# RT-Polit.net
KiCad netlist of a schematic drawn in Altium Designer
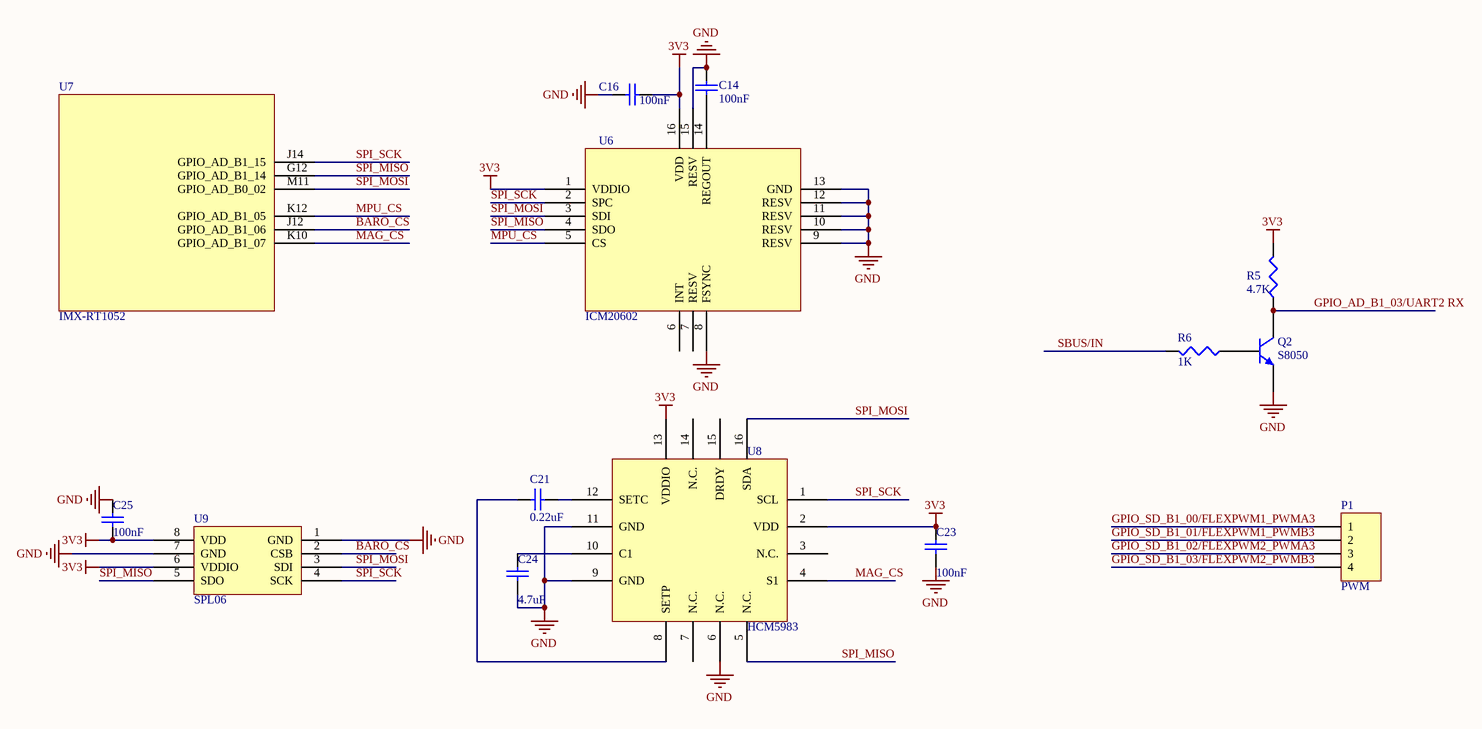
[diagram p0: RT-Polit.SchDoc]

(export (version "E")
  (design (tool "Eeschema 10.0.6"))
  (components
    (comp (ref "C14")
      (value "100nF")
      (footprint "C0402")
      (description "Capacitor (Semiconductor SIM Model)")
      (fields (field (name "PUBLISHER") "Altium Limited"))
      (libsource (lib "Miscellaneous Devices") (part "Cap Semi"))
    )
    (comp (ref "C16")
      (value "100nF")
      (footprint "C0402")
      (description "Capacitor (Semiconductor SIM Model)")
      (fields (field (name "PUBLISHER") "Altium Limited"))
      (libsource (lib "Miscellaneous Devices") (part "Cap Semi"))
    )
    (comp (ref "C21")
      (value "0.22uF")
      (footprint "C0402")
      (description "Capacitor (Semiconductor SIM Model)")
      (fields (field (name "PUBLISHER") "Altium Limited"))
      (libsource (lib "Miscellaneous Devices") (part "Cap Semi"))
    )
    (comp (ref "C23")
      (value "100nF")
      (footprint "C0402")
      (description "Capacitor (Semiconductor SIM Model)")
      (fields (field (name "PUBLISHER") "Altium Limited"))
      (libsource (lib "Miscellaneous Devices") (part "Cap Semi"))
    )
    (comp (ref "C24")
      (value "4.7uF")
      (footprint "C0402")
      (description "Capacitor (Semiconductor SIM Model)")
      (fields (field (name "PUBLISHER") "Altium Limited"))
      (libsource (lib "Miscellaneous Devices") (part "Cap Semi"))
    )
    (comp (ref "C25")
      (value "100nF")
      (footprint "C0402")
      (description "Capacitor (Semiconductor SIM Model)")
      (fields (field (name "PUBLISHER") "Altium Limited"))
      (libsource (lib "Miscellaneous Devices") (part "Cap Semi"))
    )
    (comp (ref "P1")
      (value "PWM")
      (footprint "HDR1X4H")
      (description "Header, 4-Pin, Right Angle")
      (fields (field (name "PUBLISHER") "Altium Limited"))
      (libsource (lib "Miscellaneous Connectors") (part "Header 4H"))
    )
    (comp (ref "Q2")
      (value "S8050")
      (footprint "SOT23")
      (description "NPN General Purpose Amplifier")
      (fields (field (name "PUBLISHER") "Altium Limited"))
      (libsource (lib "PCB_Project1") (part "NPN"))
    )
    (comp (ref "R5")
      (value "4.7K")
      (footprint "0603")
      (description "Resistor")
      (fields (field (name "PUBLISHER") "Altium Limited"))
      (libsource (lib "Miscellaneous Devices") (part "Res3"))
    )
    (comp (ref "R6")
      (value "1K")
      (footprint "0603")
      (description "Resistor")
      (fields (field (name "PUBLISHER") "Altium Limited"))
      (libsource (lib "Miscellaneous Devices") (part "Res3"))
    )
    (comp (ref "U6") (value "ICM20602") (footprint "QFN24") (libsource (lib "") (part "MPU6000_1")))
    (comp (ref "U7")
      (value "IMX-RT1052")
      (footprint "QFN24")
      (libsource (lib "autoquad-imu") (part "MPU6000"))
    )
    (comp (ref "U8")
      (value "HCM5983")
      (footprint "LCC16_HMC5883")
      (description "HCM5883")
      (libsource (lib "uavlib") (part "HMC5883"))
    )
    (comp (ref "U9")
      (value "SPL06")
      (footprint "MS5611-01BA")
      (libsource (lib "autoquad-imu") (part "MS5611"))
    )
  )
  (nets
    (net (code "1") (name "/BARO_CS") (class "Default")
      (node (ref "U7") (pin "J12") (pinfunction "GPIO_AD_B1_06_J12") (pintype "passive"))
      (node (ref "U9") (pin "2") (pinfunction "CSB_2") (pintype "passive"))
    )
    (net (code "2") (name "/GPIO_AD_B1_03{slash}UART2 RX") (class "Default")
      (node (ref "Q2") (pin "3") (pinfunction "C_3") (pintype "passive"))
      (node (ref "R5") (pin "1") (pinfunction "1_1") (pintype "passive"))
    )
    (net (code "3") (name "/GPIO_SD_B1_00{slash}FLEXPWM1_PWMA3") (class "Default")
      (node (ref "P1") (pin "1") (pinfunction "1_1") (pintype "passive"))
    )
    (net (code "4") (name "/GPIO_SD_B1_01{slash}FLEXPWM1_PWMB3") (class "Default")
      (node (ref "P1") (pin "2") (pinfunction "2_2") (pintype "passive"))
    )
    (net (code "5") (name "/GPIO_SD_B1_02{slash}FLEXPWM2_PWMA3") (class "Default")
      (node (ref "P1") (pin "3") (pinfunction "3_3") (pintype "passive"))
    )
    (net (code "6") (name "/GPIO_SD_B1_03{slash}FLEXPWM2_PWMB3") (class "Default")
      (node (ref "P1") (pin "4") (pinfunction "4_4") (pintype "passive"))
    )
    (net (code "7") (name "/MAG_CS") (class "Default")
      (node (ref "U7") (pin "K10") (pinfunction "GPIO_AD_B1_07_K10") (pintype "passive"))
      (node (ref "U8") (pin "4") (pinfunction "S1_4") (pintype "passive"))
    )
    (net (code "8") (name "/MPU_CS") (class "Default")
      (node (ref "U6") (pin "5") (pinfunction "CS_5") (pintype "passive"))
      (node (ref "U7") (pin "K12") (pinfunction "GPIO_AD_B1_05_K12") (pintype "passive"))
    )
    (net (code "9") (name "/SBUS{slash}IN") (class "Default")
      (node (ref "R6") (pin "2") (pinfunction "2_2") (pintype "passive"))
    )
    (net (code "10") (name "/SPI_MISO") (class "Default")
      (node (ref "U6") (pin "4") (pinfunction "SDO_4") (pintype "passive"))
      (node (ref "U7") (pin "G12") (pinfunction "GPIO_AD_B1_14_G12") (pintype "passive"))
      (node (ref "U8") (pin "5") (pinfunction "N.C._5") (pintype "passive"))
      (node (ref "U9") (pin "5") (pinfunction "SDO_5") (pintype "passive"))
    )
    (net (code "11") (name "/SPI_MOSI") (class "Default")
      (node (ref "U6") (pin "3") (pinfunction "SDI_3") (pintype "passive"))
      (node (ref "U7") (pin "M11") (pinfunction "GPIO_AD_B0_02_M11") (pintype "passive"))
      (node (ref "U8") (pin "16") (pinfunction "SDA_16") (pintype "passive"))
      (node (ref "U9") (pin "3") (pinfunction "SDI_3") (pintype "passive"))
    )
    (net (code "12") (name "/SPI_SCK") (class "Default")
      (node (ref "U6") (pin "2") (pinfunction "SPC_2") (pintype "passive"))
      (node (ref "U7") (pin "J14") (pinfunction "GPIO_AD_B1_15_J14") (pintype "passive"))
      (node (ref "U8") (pin "1") (pinfunction "SCL_1") (pintype "passive"))
      (node (ref "U9") (pin "4") (pinfunction "SCK_4") (pintype "power_in"))
    )
    (net (code "13") (name "3V3") (class "Default")
      (node (ref "C16") (pin "2") (pinfunction "2_2") (pintype "passive"))
      (node (ref "C23") (pin "1") (pinfunction "1_1") (pintype "passive"))
      (node (ref "C25") (pin "2") (pinfunction "2_2") (pintype "passive"))
      (node (ref "R5") (pin "2") (pinfunction "2_2") (pintype "passive"))
      (node (ref "U6") (pin "1") (pinfunction "VDDIO_1") (pintype "passive"))
      (node (ref "U6") (pin "16") (pinfunction "VDD_16") (pintype "passive"))
      (node (ref "U8") (pin "13") (pinfunction "VDDIO_13") (pintype "passive"))
      (node (ref "U8") (pin "2") (pinfunction "VDD_2") (pintype "passive"))
      (node (ref "U9") (pin "6") (pinfunction "VDDIO_6") (pintype "passive"))
      (node (ref "U9") (pin "8") (pinfunction "VDD_8") (pintype "power_in"))
    )
    (net (code "14") (name "GND") (class "Default")
      (node (ref "C14") (pin "2") (pinfunction "2_2") (pintype "passive"))
      (node (ref "C16") (pin "1") (pinfunction "1_1") (pintype "passive"))
      (node (ref "C23") (pin "2") (pinfunction "2_2") (pintype "passive"))
      (node (ref "C24") (pin "2") (pinfunction "2_2") (pintype "passive"))
      (node (ref "C25") (pin "1") (pinfunction "1_1") (pintype "passive"))
      (node (ref "Q2") (pin "2") (pinfunction "E_2") (pintype "passive"))
      (node (ref "U6") (pin "10") (pinfunction "RESV_10") (pintype "passive"))
      (node (ref "U6") (pin "11") (pinfunction "RESV_11") (pintype "passive"))
      (node (ref "U6") (pin "12") (pinfunction "RESV_12") (pintype "passive"))
      (node (ref "U6") (pin "13") (pinfunction "GND_13") (pintype "passive"))
      (node (ref "U6") (pin "15") (pinfunction "RESV_15") (pintype "passive"))
      (node (ref "U6") (pin "8") (pinfunction "FSYNC_8") (pintype "passive"))
      (node (ref "U6") (pin "9") (pinfunction "RESV_9") (pintype "passive"))
      (node (ref "U8") (pin "11") (pinfunction "GND_11") (pintype "passive"))
      (node (ref "U8") (pin "6") (pinfunction "N.C._6") (pintype "passive"))
      (node (ref "U8") (pin "9") (pinfunction "GND_9") (pintype "passive"))
      (node (ref "U9") (pin "1") (pinfunction "GND_1") (pintype "passive"))
      (node (ref "U9") (pin "7") (pinfunction "GND_7") (pintype "passive"))
    )
    (net (code "15") (name "Net-(Q2-B)") (class "Default")
      (node (ref "Q2") (pin "1") (pinfunction "B_1") (pintype "passive"))
      (node (ref "R6") (pin "1") (pinfunction "1_1") (pintype "passive"))
    )
    (net (code "16") (name "Net-(U6-REGOUT)") (class "Default")
      (node (ref "C14") (pin "1") (pinfunction "1_1") (pintype "passive"))
      (node (ref "U6") (pin "14") (pinfunction "REGOUT_14") (pintype "passive"))
    )
    (net (code "17") (name "Net-(U8-C1)") (class "Default")
      (node (ref "C24") (pin "1") (pinfunction "1_1") (pintype "passive"))
      (node (ref "U8") (pin "10") (pinfunction "C1_10") (pintype "passive"))
    )
    (net (code "18") (name "Net-(U8-SETC)") (class "Default")
      (node (ref "C21") (pin "2") (pinfunction "2_2") (pintype "passive"))
      (node (ref "U8") (pin "12") (pinfunction "SETC_12") (pintype "passive"))
    )
    (net (code "19") (name "Net-(U8-SETP)") (class "Default")
      (node (ref "C21") (pin "1") (pinfunction "1_1") (pintype "passive"))
      (node (ref "U8") (pin "8") (pinfunction "SETP_8") (pintype "passive"))
    )
    (net (code "20") (name "unconnected-(U6-INT-Pad6)") (class "Default")
      (node (ref "U6") (pin "6") (pinfunction "INT_6") (pintype "passive"))
    )
    (net (code "21") (name "unconnected-(U6-RESV-Pad7)") (class "Default")
      (node (ref "U6") (pin "7") (pinfunction "RESV_7") (pintype "passive"))
    )
    (net (code "22") (name "unconnected-(U8-DRDY-Pad15)") (class "Default")
      (node (ref "U8") (pin "15") (pinfunction "DRDY_15") (pintype "passive"))
    )
    (net (code "23") (name "unconnected-(U8-N.C.-Pad3)") (class "Default")
      (node (ref "U8") (pin "3") (pinfunction "N.C._3") (pintype "passive"))
    )
    (net (code "24") (name "unconnected-(U8-N.C.-Pad7)") (class "Default")
      (node (ref "U8") (pin "7") (pinfunction "N.C._7") (pintype "passive"))
    )
    (net (code "25") (name "unconnected-(U8-N.C.-Pad14)") (class "Default")
      (node (ref "U8") (pin "14") (pinfunction "N.C._14") (pintype "passive"))
    )
  )
)
